# octanis_eps_v04.net
KiCad netlist of a schematic drawn in EAGLE
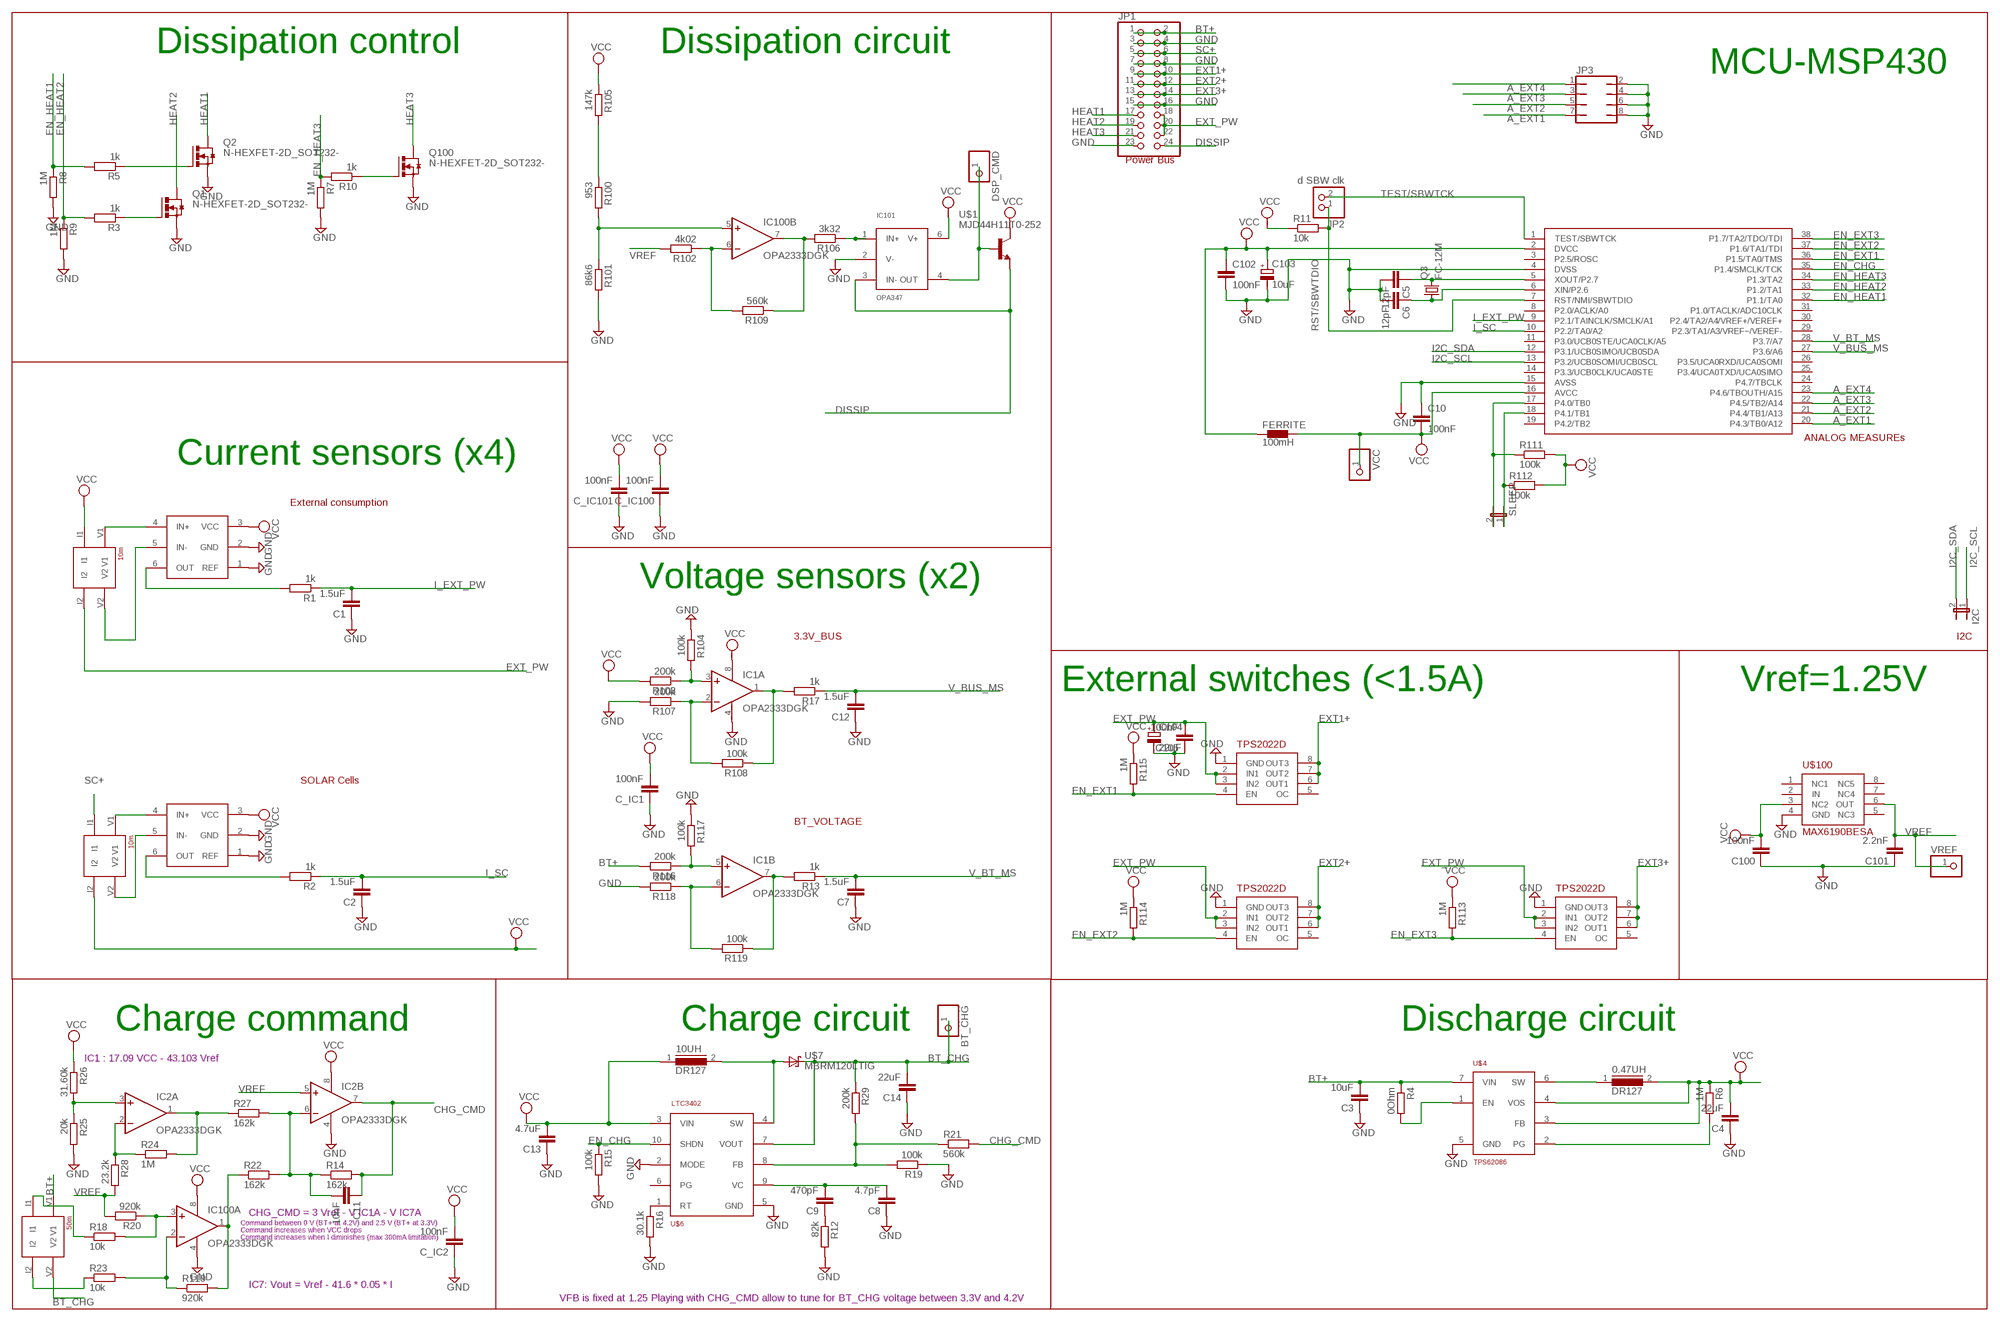
[diagram p0: schematic, sheet 1]

(export (version "E")
  (design (tool "Eeschema 10.0.6"))
  (components
    (comp (ref "0.47UH")
      (value "DR127")
      (footprint "eagle-import:DR127")
      (libsource (lib "eagle-import") (part "DR127"))
    )
    (comp (ref "10UH")
      (value "DR127")
      (footprint "eagle-import:DR127")
      (libsource (lib "eagle-import") (part "DR127"))
    )
    (comp (ref "BT_CHG")
      (value "PINHD-1X1")
      (footprint "eagle-import:1X01")
      (libsource (lib "eagle-import") (part "PINHD-1X1"))
    )
    (comp (ref "C1")
      (value "1.5uF")
      (footprint "eagle-import:C0603")
      (libsource (lib "eagle-import") (part "C-EUC0603"))
    )
    (comp (ref "C2")
      (value "1.5uF")
      (footprint "eagle-import:C0603")
      (libsource (lib "eagle-import") (part "C-EUC0603"))
    )
    (comp (ref "C3")
      (value "10uF")
      (footprint "eagle-import:C1206")
      (libsource (lib "eagle-import") (part "C-EUC1206"))
    )
    (comp (ref "C4")
      (value "22uF")
      (footprint "eagle-import:C1206")
      (libsource (lib "eagle-import") (part "C-EUC1206"))
    )
    (comp (ref "C5")
      (value "12pF")
      (footprint "eagle-import:C0603")
      (libsource (lib "eagle-import") (part "C-EUC0603"))
    )
    (comp (ref "C6")
      (value "12pF")
      (footprint "eagle-import:C0603")
      (libsource (lib "eagle-import") (part "C-EUC0603"))
    )
    (comp (ref "C7")
      (value "1.5uF")
      (footprint "eagle-import:C0603")
      (libsource (lib "eagle-import") (part "C-EUC0603"))
    )
    (comp (ref "C8")
      (value "4.7pF")
      (footprint "eagle-import:C0603")
      (libsource (lib "eagle-import") (part "C-EUC0603"))
    )
    (comp (ref "C9")
      (value "470pF")
      (footprint "eagle-import:C0603")
      (libsource (lib "eagle-import") (part "C-EUC0603"))
    )
    (comp (ref "C10")
      (value "100nF")
      (footprint "eagle-import:C0603")
      (libsource (lib "eagle-import") (part "C-EUC0603"))
    )
    (comp (ref "C11")
      (value "10nF")
      (footprint "eagle-import:C0603")
      (libsource (lib "eagle-import") (part "C-EUC0603"))
    )
    (comp (ref "C12")
      (value "1.5uF")
      (footprint "eagle-import:C0603")
      (libsource (lib "eagle-import") (part "C-EUC0603"))
    )
    (comp (ref "C13")
      (value "4.7uF")
      (footprint "eagle-import:C1206")
      (libsource (lib "eagle-import") (part "C-EUC1206"))
    )
    (comp (ref "C14")
      (value "22uF")
      (footprint "eagle-import:C0603")
      (libsource (lib "eagle-import") (part "C-EUC0603"))
    )
    (comp (ref "C100")
      (value "100nF")
      (footprint "eagle-import:C0603")
      (libsource (lib "eagle-import") (part "C-EUC0603"))
    )
    (comp (ref "C101")
      (value "2.2nF")
      (footprint "eagle-import:C0603")
      (libsource (lib "eagle-import") (part "C-EUC0603"))
    )
    (comp (ref "C102")
      (value "100nF")
      (footprint "eagle-import:C0603")
      (libsource (lib "eagle-import") (part "C-EUC0603"))
    )
    (comp (ref "C103")
      (value "10uF")
      (footprint "eagle-import:A_3216-18R")
      (libsource (lib "eagle-import") (part "CPOL-EUA/3216-18R"))
    )
    (comp (ref "C104")
      (value "22uF")
      (footprint "eagle-import:A_3216-18R")
      (libsource (lib "eagle-import") (part "CPOL-EUA/3216-18R"))
    )
    (comp (ref "C105")
      (value "100nF")
      (footprint "eagle-import:C0603")
      (libsource (lib "eagle-import") (part "C-EUC0603"))
    )
    (comp (ref "C_IC1")
      (value "100nF")
      (footprint "eagle-import:C0603")
      (libsource (lib "eagle-import") (part "C-EUC0603"))
    )
    (comp (ref "C_IC2")
      (value "100nF")
      (footprint "eagle-import:C0603")
      (libsource (lib "eagle-import") (part "C-EUC0603"))
    )
    (comp (ref "C_IC100")
      (value "100nF")
      (footprint "eagle-import:C0603")
      (libsource (lib "eagle-import") (part "C-EUC0603"))
    )
    (comp (ref "C_IC101")
      (value "100nF")
      (footprint "eagle-import:C0603")
      (libsource (lib "eagle-import") (part "C-EUC0603"))
    )
    (comp (ref "DSP_CMD")
      (value "PINHD-1X1")
      (footprint "eagle-import:1X01")
      (libsource (lib "eagle-import") (part "PINHD-1X1"))
    )
    (comp (ref "FERRITE")
      (value "100mH")
      (footprint "eagle-import:0402")
      (libsource (lib "eagle-import") (part "BLM15HD601SN1"))
    )
    (comp (ref "I2C")
      (value "JP1E")
      (footprint "eagle-import:JP1")
      (libsource (lib "eagle-import") (part "JP1E"))
    )
    (comp (ref "IC1")
      (value "OPA2333DGK")
      (footprint "eagle-import:MSOP08")
      (libsource (lib "eagle-import") (part "OPA2333DGK"))
    )
    (comp (ref "IC2")
      (value "OPA2333DGK")
      (footprint "eagle-import:MSOP08")
      (libsource (lib "eagle-import") (part "OPA2333DGK"))
    )
    (comp (ref "IC100")
      (value "OPA2333DGK")
      (footprint "eagle-import:MSOP08")
      (libsource (lib "eagle-import") (part "OPA2333DGK"))
    )
    (comp (ref "IC101")
      (value "OPA347")
      (footprint "eagle-import:SC70-5")
      (libsource (lib "eagle-import") (part "OPA347"))
    )
    (comp (ref "JP1")
      (value "PINHD-2X12")
      (footprint "eagle-import:2X12")
      (libsource (lib "eagle-import") (part "PINHD-2X12"))
    )
    (comp (ref "JP2")
      (value "d SBW clk")
      (footprint "eagle-import:1X02")
      (libsource (lib "eagle-import") (part "PINHD-1X2"))
    )
    (comp (ref "JP3")
      (value "JP4Q")
      (footprint "eagle-import:JP4Q")
      (libsource (lib "eagle-import") (part "JP4Q"))
    )
    (comp (ref "Q1")
      (value "N-HEXFET-2D_SOT232-")
      (footprint "eagle-import:SOT223")
      (libsource (lib "eagle-import") (part "N-HEXFET-2D_?-SOT232"))
    )
    (comp (ref "Q2")
      (value "N-HEXFET-2D_SOT232-")
      (footprint "eagle-import:SOT223")
      (libsource (lib "eagle-import") (part "N-HEXFET-2D_?-SOT232"))
    )
    (comp (ref "Q3")
      (value "FC-12M")
      (footprint "eagle-import:FC-12M")
      (libsource (lib "eagle-import") (part "FC-12M"))
    )
    (comp (ref "Q100")
      (value "N-HEXFET-2D_SOT232-")
      (footprint "eagle-import:SOT223")
      (libsource (lib "eagle-import") (part "N-HEXFET-2D_?-SOT232"))
    )
    (comp (ref "R1")
      (value "1k")
      (footprint "eagle-import:R0603")
      (libsource (lib "eagle-import") (part "R-EU_R0603"))
    )
    (comp (ref "R2")
      (value "1k")
      (footprint "eagle-import:R0603")
      (libsource (lib "eagle-import") (part "R-EU_R0603"))
    )
    (comp (ref "R3")
      (value "1k")
      (footprint "eagle-import:R0603")
      (libsource (lib "eagle-import") (part "R-EU_R0603"))
    )
    (comp (ref "R4")
      (value "0Ohm")
      (footprint "eagle-import:R0603")
      (libsource (lib "eagle-import") (part "R-EU_R0603"))
    )
    (comp (ref "R5")
      (value "1k")
      (footprint "eagle-import:R0603")
      (libsource (lib "eagle-import") (part "R-EU_R0603"))
    )
    (comp (ref "R6")
      (value "1M")
      (footprint "eagle-import:R0603")
      (libsource (lib "eagle-import") (part "R-EU_R0603"))
    )
    (comp (ref "R7")
      (value "1M")
      (footprint "eagle-import:R0603")
      (libsource (lib "eagle-import") (part "R-EU_R0603"))
    )
    (comp (ref "R8")
      (value "1M")
      (footprint "eagle-import:R0603")
      (libsource (lib "eagle-import") (part "R-EU_R0603"))
    )
    (comp (ref "R9")
      (value "1M")
      (footprint "eagle-import:R0603")
      (libsource (lib "eagle-import") (part "R-EU_R0603"))
    )
    (comp (ref "R10")
      (value "1k")
      (footprint "eagle-import:R0603")
      (libsource (lib "eagle-import") (part "R-EU_R0603"))
    )
    (comp (ref "R11")
      (value "10k")
      (footprint "eagle-import:R0603")
      (libsource (lib "eagle-import") (part "R-EU_R0603"))
    )
    (comp (ref "R12")
      (value "82k")
      (footprint "eagle-import:R0603")
      (libsource (lib "eagle-import") (part "R-EU_R0603"))
    )
    (comp (ref "R13")
      (value "1k")
      (footprint "eagle-import:R0603")
      (libsource (lib "eagle-import") (part "R-EU_R0603"))
    )
    (comp (ref "R14")
      (value "162k")
      (footprint "eagle-import:R0603")
      (libsource (lib "eagle-import") (part "R-EU_R0603"))
    )
    (comp (ref "R15")
      (value "100k")
      (footprint "eagle-import:R0603")
      (libsource (lib "eagle-import") (part "R-EU_R0603"))
    )
    (comp (ref "R16")
      (value "30.1k")
      (footprint "eagle-import:R0603")
      (libsource (lib "eagle-import") (part "R-EU_R0603"))
    )
    (comp (ref "R17")
      (value "1k")
      (footprint "eagle-import:R0603")
      (libsource (lib "eagle-import") (part "R-EU_R0603"))
    )
    (comp (ref "R18")
      (value "10k")
      (footprint "eagle-import:R0603")
      (libsource (lib "eagle-import") (part "R-EU_R0603"))
    )
    (comp (ref "R19")
      (value "100k")
      (footprint "eagle-import:R0603")
      (libsource (lib "eagle-import") (part "R-EU_R0603"))
    )
    (comp (ref "R20")
      (value "920k")
      (footprint "eagle-import:R0603")
      (libsource (lib "eagle-import") (part "R-EU_R0603"))
    )
    (comp (ref "R21")
      (value "560k")
      (footprint "eagle-import:R0603")
      (libsource (lib "eagle-import") (part "R-EU_R0603"))
    )
    (comp (ref "R22")
      (value "162k")
      (footprint "eagle-import:R0603")
      (libsource (lib "eagle-import") (part "R-EU_R0603"))
    )
    (comp (ref "R23")
      (value "10k")
      (footprint "eagle-import:R0603")
      (libsource (lib "eagle-import") (part "R-EU_R0603"))
    )
    (comp (ref "R24")
      (value "1M")
      (footprint "eagle-import:R0603")
      (libsource (lib "eagle-import") (part "R-EU_R0603"))
    )
    (comp (ref "R25")
      (value "20k")
      (footprint "eagle-import:R0603")
      (libsource (lib "eagle-import") (part "R-EU_R0603"))
    )
    (comp (ref "R26")
      (value "31.60k")
      (footprint "eagle-import:R0603")
      (libsource (lib "eagle-import") (part "R-EU_R0603"))
    )
    (comp (ref "R27")
      (value "162k")
      (footprint "eagle-import:R0603")
      (libsource (lib "eagle-import") (part "R-EU_R0603"))
    )
    (comp (ref "R28")
      (value "23.2k")
      (footprint "eagle-import:R0603")
      (libsource (lib "eagle-import") (part "R-EU_R0603"))
    )
    (comp (ref "R29")
      (value "200k")
      (footprint "eagle-import:R0603")
      (libsource (lib "eagle-import") (part "R-EU_R0603"))
    )
    (comp (ref "R100")
      (value "953")
      (footprint "eagle-import:R0603")
      (libsource (lib "eagle-import") (part "R-EU_R0603"))
    )
    (comp (ref "R101")
      (value "86k6")
      (footprint "eagle-import:R0603")
      (libsource (lib "eagle-import") (part "R-EU_R0603"))
    )
    (comp (ref "R102")
      (value "4k02")
      (footprint "eagle-import:R0603")
      (libsource (lib "eagle-import") (part "R-EU_R0603"))
    )
    (comp (ref "R103")
      (value "200k")
      (footprint "eagle-import:R0603")
      (libsource (lib "eagle-import") (part "R-EU_R0603"))
    )
    (comp (ref "R104")
      (value "100k")
      (footprint "eagle-import:R0603")
      (libsource (lib "eagle-import") (part "R-EU_R0603"))
    )
    (comp (ref "R105")
      (value "147k")
      (footprint "eagle-import:R0603")
      (libsource (lib "eagle-import") (part "R-EU_R0603"))
    )
    (comp (ref "R106")
      (value "3k32")
      (footprint "eagle-import:R0603")
      (libsource (lib "eagle-import") (part "R-EU_R0603"))
    )
    (comp (ref "R107")
      (value "200k")
      (footprint "eagle-import:R0603")
      (libsource (lib "eagle-import") (part "R-EU_R0603"))
    )
    (comp (ref "R108")
      (value "100k")
      (footprint "eagle-import:R0603")
      (libsource (lib "eagle-import") (part "R-EU_R0603"))
    )
    (comp (ref "R109")
      (value "560k")
      (footprint "eagle-import:R0603")
      (libsource (lib "eagle-import") (part "R-EU_R0603"))
    )
    (comp (ref "R110")
      (value "920k")
      (footprint "eagle-import:R0603")
      (libsource (lib "eagle-import") (part "R-EU_R0603"))
    )
    (comp (ref "R111")
      (value "100k")
      (footprint "eagle-import:R0603")
      (libsource (lib "eagle-import") (part "R-EU_R0603"))
    )
    (comp (ref "R112")
      (value "100k")
      (footprint "eagle-import:R0603")
      (libsource (lib "eagle-import") (part "R-EU_R0603"))
    )
    (comp (ref "R113")
      (value "1M")
      (footprint "eagle-import:R0603")
      (libsource (lib "eagle-import") (part "R-EU_R0603"))
    )
    (comp (ref "R114")
      (value "1M")
      (footprint "eagle-import:R0603")
      (libsource (lib "eagle-import") (part "R-EU_R0603"))
    )
    (comp (ref "R115")
      (value "1M")
      (footprint "eagle-import:R0603")
      (libsource (lib "eagle-import") (part "R-EU_R0603"))
    )
    (comp (ref "R116")
      (value "200k")
      (footprint "eagle-import:R0603")
      (libsource (lib "eagle-import") (part "R-EU_R0603"))
    )
    (comp (ref "R117")
      (value "100k")
      (footprint "eagle-import:R0603")
      (libsource (lib "eagle-import") (part "R-EU_R0603"))
    )
    (comp (ref "R118")
      (value "200k")
      (footprint "eagle-import:R0603")
      (libsource (lib "eagle-import") (part "R-EU_R0603"))
    )
    (comp (ref "R119")
      (value "100k")
      (footprint "eagle-import:R0603")
      (libsource (lib "eagle-import") (part "R-EU_R0603"))
    )
    (comp (ref "RSENSE1")
      (value "10m")
      (footprint "eagle-import:4PADS_RESISTOR")
      (libsource (lib "eagle-import") (part "CURRENT_RESISTOR"))
    )
    (comp (ref "RSENSE2")
      (value "50m")
      (footprint "eagle-import:4PADS_RESISTOR")
      (libsource (lib "eagle-import") (part "CURRENT_RESISTOR"))
    )
    (comp (ref "R_SENSE1")
      (value "10m")
      (footprint "eagle-import:4PADS_RESISTOR")
      (libsource (lib "eagle-import") (part "CURRENT_RESISTOR"))
    )
    (comp (ref "SLEEP")
      (value "JP1E")
      (footprint "eagle-import:JP1")
      (libsource (lib "eagle-import") (part "JP1E"))
    )
    (comp (ref "U$1")
      (value "MJD44H11T0-252")
      (footprint "eagle-import:TO252")
      (libsource (lib "eagle-import") (part "MJD44H11T0-252"))
    )
    (comp (ref "U$2")
      (value "INA213")
      (footprint "eagle-import:SC70-6")
      (libsource (lib "eagle-import") (part "INA213"))
    )
    (comp (ref "U$3")
      (value "INA213")
      (footprint "eagle-import:SC70-6")
      (libsource (lib "eagle-import") (part "INA213"))
    )
    (comp (ref "U$4")
      (value "TPS62086")
      (footprint "eagle-import:QFN-7")
      (libsource (lib "eagle-import") (part "TPS62086"))
    )
    (comp (ref "U$5")
      (value "MSP430G2544")
      (footprint "eagle-import:TSSOP38_MSPGXX44_SERIES")
      (libsource (lib "eagle-import") (part "MSP430G2544"))
    )
    (comp (ref "U$6")
      (value "LTC3402")
      (footprint "eagle-import:MSOP10")
      (libsource (lib "eagle-import") (part "LTC3402"))
    )
    (comp (ref "U$7")
      (value "MBRM120LTIG")
      (footprint "eagle-import:DO216AA")
      (libsource (lib "eagle-import") (part "MBRM120LTIG"))
    )
    (comp (ref "U$100")
      (value "MAX6190BESA")
      (footprint "eagle-import:SO8")
      (libsource (lib "eagle-import") (part "MAX6190BESA"))
    )
    (comp (ref "U$101")
      (value "TPS2022D")
      (footprint "eagle-import:SO8")
      (libsource (lib "eagle-import") (part "TPS2022D"))
    )
    (comp (ref "U$102")
      (value "TPS2022D")
      (footprint "eagle-import:SO8")
      (libsource (lib "eagle-import") (part "TPS2022D"))
    )
    (comp (ref "U$103")
      (value "TPS2022D")
      (footprint "eagle-import:SO8")
      (libsource (lib "eagle-import") (part "TPS2022D"))
    )
    (comp (ref "VCC")
      (value "PINHD-1X1")
      (footprint "eagle-import:1X01")
      (libsource (lib "eagle-import") (part "PINHD-1X1"))
    )
    (comp (ref "VREF")
      (value "PINHD-1X1")
      (footprint "eagle-import:1X01")
      (libsource (lib "eagle-import") (part "PINHD-1X1"))
    )
  )
  (nets
    (net (code "1") (name "/A_EXT1") (class "Default")
      (node (ref "JP3") (pin "7") (pinfunction "7_7") (pintype "passive"))
      (node (ref "U$5") (pin "20") (pinfunction "P4.3/TB0/A12_20") (pintype "bidirectional"))
    )
    (net (code "2") (name "/A_EXT2") (class "Default")
      (node (ref "JP3") (pin "5") (pinfunction "5_5") (pintype "passive"))
      (node (ref "U$5") (pin "21") (pinfunction "P4.4/TB1/A13_21") (pintype "bidirectional"))
    )
    (net (code "3") (name "/A_EXT3") (class "Default")
      (node (ref "JP3") (pin "3") (pinfunction "3_3") (pintype "passive"))
      (node (ref "U$5") (pin "22") (pinfunction "P4.5/TB2/A14_22") (pintype "bidirectional"))
    )
    (net (code "4") (name "/A_EXT4") (class "Default")
      (node (ref "JP3") (pin "1") (pinfunction "1_1") (pintype "passive"))
      (node (ref "U$5") (pin "23") (pinfunction "P4.6/TBOUTH/A15_23") (pintype "bidirectional"))
    )
    (net (code "5") (name "/BT+") (class "Default")
      (node (ref "C3") (pin "2") (pinfunction "2_2") (pintype "passive"))
      (node (ref "JP1") (pin "1") (pinfunction "1_1") (pintype "passive"))
      (node (ref "JP1") (pin "2") (pinfunction "2_2") (pintype "passive"))
      (node (ref "R116") (pin "2") (pinfunction "2_2") (pintype "passive"))
      (node (ref "R4") (pin "1") (pinfunction "1_1") (pintype "passive"))
      (node (ref "RSENSE2") (pin "V1") (pinfunction "V1_V1") (pintype "bidirectional"))
      (node (ref "U$4") (pin "7") (pinfunction "VIN_7") (pintype "bidirectional"))
    )
    (net (code "6") (name "/BT_CHG") (class "Default")
      (node (ref "BT_CHG") (pin "1") (pinfunction "1_1") (pintype "passive"))
      (node (ref "C14") (pin "2") (pinfunction "2_2") (pintype "passive"))
      (node (ref "R29") (pin "1") (pinfunction "1_1") (pintype "passive"))
      (node (ref "RSENSE2") (pin "V2") (pinfunction "V2_V2") (pintype "bidirectional"))
      (node (ref "U$6") (pin "7") (pinfunction "VOUT_7") (pintype "bidirectional"))
      (node (ref "U$7") (pin "C") (pinfunction "K_C") (pintype "passive"))
    )
    (net (code "7") (name "/CHG_CMD") (class "Default")
      (node (ref "C11") (pin "1") (pinfunction "1_1") (pintype "passive"))
      (node (ref "IC2") (pin "7") (pinfunction "OUT_7") (pintype "output"))
      (node (ref "R14") (pin "2") (pinfunction "2_2") (pintype "passive"))
      (node (ref "R21") (pin "2") (pinfunction "2_2") (pintype "passive"))
    )
    (net (code "8") (name "/DISSIP") (class "Default")
      (node (ref "IC101") (pin "3") (pinfunction "IN-_3") (pintype "bidirectional"))
      (node (ref "JP1") (pin "24") (pinfunction "24_24") (pintype "passive"))
      (node (ref "U$1") (pin "3") (pinfunction "E_3") (pintype "passive"))
    )
    (net (code "9") (name "/EN_CHG") (class "Default")
      (node (ref "R15") (pin "1") (pinfunction "1_1") (pintype "passive"))
      (node (ref "U$5") (pin "35") (pinfunction "P1.4/SMCLK/TCK_35") (pintype "bidirectional"))
      (node (ref "U$6") (pin "10") (pinfunction "SHDN_10") (pintype "bidirectional"))
    )
    (net (code "10") (name "/EN_EXT1") (class "Default")
      (node (ref "R115") (pin "2") (pinfunction "2_2") (pintype "passive"))
      (node (ref "U$103") (pin "4") (pinfunction "EN_4") (pintype "bidirectional"))
      (node (ref "U$5") (pin "36") (pinfunction "P1.5/TA0/TMS_36") (pintype "bidirectional"))
    )
    (net (code "11") (name "/EN_EXT2") (class "Default")
      (node (ref "R114") (pin "2") (pinfunction "2_2") (pintype "passive"))
      (node (ref "U$102") (pin "4") (pinfunction "EN_4") (pintype "bidirectional"))
      (node (ref "U$5") (pin "37") (pinfunction "P1.6/TA1/TDI_37") (pintype "bidirectional"))
    )
    (net (code "12") (name "/EN_EXT3") (class "Default")
      (node (ref "R113") (pin "2") (pinfunction "2_2") (pintype "passive"))
      (node (ref "U$101") (pin "4") (pinfunction "EN_4") (pintype "bidirectional"))
      (node (ref "U$5") (pin "38") (pinfunction "P1.7/TA2/TDO/TDI_38") (pintype "bidirectional"))
    )
    (net (code "13") (name "/EN_HEAT1") (class "Default")
      (node (ref "R5") (pin "2") (pinfunction "2_2") (pintype "passive"))
      (node (ref "R8") (pin "1") (pinfunction "1_1") (pintype "passive"))
      (node (ref "U$5") (pin "32") (pinfunction "P1.1/TA0_32") (pintype "bidirectional"))
    )
    (net (code "14") (name "/EN_HEAT2") (class "Default")
      (node (ref "R3") (pin "2") (pinfunction "2_2") (pintype "passive"))
      (node (ref "R9") (pin "1") (pinfunction "1_1") (pintype "passive"))
      (node (ref "U$5") (pin "33") (pinfunction "P1.2/TA1_33") (pintype "bidirectional"))
    )
    (net (code "15") (name "/EN_HEAT3") (class "Default")
      (node (ref "R10") (pin "2") (pinfunction "2_2") (pintype "passive"))
      (node (ref "R7") (pin "1") (pinfunction "1_1") (pintype "passive"))
      (node (ref "U$5") (pin "34") (pinfunction "P1.3/TA2_34") (pintype "bidirectional"))
    )
    (net (code "16") (name "/EXT1+") (class "Default")
      (node (ref "JP1") (pin "10") (pinfunction "10_10") (pintype "passive"))
      (node (ref "JP1") (pin "9") (pinfunction "9_9") (pintype "passive"))
      (node (ref "U$103") (pin "6") (pinfunction "OUT1_6") (pintype "bidirectional"))
      (node (ref "U$103") (pin "7") (pinfunction "OUT2_7") (pintype "bidirectional"))
      (node (ref "U$103") (pin "8") (pinfunction "OUT3_8") (pintype "bidirectional"))
    )
    (net (code "17") (name "/EXT2+") (class "Default")
      (node (ref "JP1") (pin "11") (pinfunction "11_11") (pintype "passive"))
      (node (ref "JP1") (pin "12") (pinfunction "12_12") (pintype "passive"))
      (node (ref "U$102") (pin "6") (pinfunction "OUT1_6") (pintype "bidirectional"))
      (node (ref "U$102") (pin "7") (pinfunction "OUT2_7") (pintype "bidirectional"))
      (node (ref "U$102") (pin "8") (pinfunction "OUT3_8") (pintype "bidirectional"))
    )
    (net (code "18") (name "/EXT3+") (class "Default")
      (node (ref "JP1") (pin "13") (pinfunction "13_13") (pintype "passive"))
      (node (ref "JP1") (pin "14") (pinfunction "14_14") (pintype "passive"))
      (node (ref "U$101") (pin "6") (pinfunction "OUT1_6") (pintype "bidirectional"))
      (node (ref "U$101") (pin "7") (pinfunction "OUT2_7") (pintype "bidirectional"))
      (node (ref "U$101") (pin "8") (pinfunction "OUT3_8") (pintype "bidirectional"))
    )
    (net (code "19") (name "/EXT_PW") (class "Default")
      (node (ref "C104") (pin "+") (pinfunction "+_+") (pintype "passive"))
      (node (ref "C105") (pin "2") (pinfunction "2_2") (pintype "passive"))
      (node (ref "JP1") (pin "18") (pinfunction "18_18") (pintype "passive"))
      (node (ref "JP1") (pin "20") (pinfunction "20_20") (pintype "passive"))
      (node (ref "JP1") (pin "22") (pinfunction "22_22") (pintype "passive"))
      (node (ref "R_SENSE1") (pin "I2") (pinfunction "I2_I2") (pintype "bidirectional"))
      (node (ref "U$101") (pin "2") (pinfunction "IN1_2") (pintype "bidirectional"))
      (node (ref "U$101") (pin "3") (pinfunction "IN2_3") (pintype "bidirectional"))
      (node (ref "U$102") (pin "2") (pinfunction "IN1_2") (pintype "bidirectional"))
      (node (ref "U$102") (pin "3") (pinfunction "IN2_3") (pintype "bidirectional"))
      (node (ref "U$103") (pin "2") (pinfunction "IN1_2") (pintype "bidirectional"))
      (node (ref "U$103") (pin "3") (pinfunction "IN2_3") (pintype "bidirectional"))
    )
    (net (code "20") (name "/HEAT1") (class "Default")
      (node (ref "JP1") (pin "17") (pinfunction "17_17") (pintype "passive"))
      (node (ref "Q2") (pin "2") (pinfunction "D_2") (pintype "passive"))
      (node (ref "Q2") (pin "4") (pinfunction "D_4") (pintype "passive"))
    )
    (net (code "21") (name "/HEAT2") (class "Default")
      (node (ref "JP1") (pin "19") (pinfunction "19_19") (pintype "passive"))
      (node (ref "Q1") (pin "2") (pinfunction "D_2") (pintype "passive"))
      (node (ref "Q1") (pin "4") (pinfunction "D_4") (pintype "passive"))
    )
    (net (code "22") (name "/HEAT3") (class "Default")
      (node (ref "JP1") (pin "21") (pinfunction "21_21") (pintype "passive"))
      (node (ref "Q100") (pin "2") (pinfunction "D_2") (pintype "passive"))
      (node (ref "Q100") (pin "4") (pinfunction "D_4") (pintype "passive"))
    )
    (net (code "23") (name "/I2C_SCL") (class "Default")
      (node (ref "I2C") (pin "1") (pinfunction "1_1") (pintype "passive"))
      (node (ref "U$5") (pin "13") (pinfunction "P3.2/UCB0SOMI/UCB0SCL_13") (pintype "bidirectional"))
    )
    (net (code "24") (name "/I2C_SDA") (class "Default")
      (node (ref "I2C") (pin "2") (pinfunction "2_2") (pintype "passive"))
      (node (ref "U$5") (pin "12") (pinfunction "P3.1/UCB0SIMO/UCB0SDA_12") (pintype "bidirectional"))
    )
    (net (code "25") (name "/I_EXT_PW") (class "Default")
      (node (ref "C1") (pin "2") (pinfunction "2_2") (pintype "passive"))
      (node (ref "R1") (pin "1") (pinfunction "1_1") (pintype "passive"))
      (node (ref "U$5") (pin "9") (pinfunction "P2.1/TAINCLK/SMCLK/A1_9") (pintype "bidirectional"))
    )
    (net (code "26") (name "/I_SC") (class "Default")
      (node (ref "C2") (pin "2") (pinfunction "2_2") (pintype "passive"))
      (node (ref "R2") (pin "1") (pinfunction "1_1") (pintype "passive"))
      (node (ref "U$5") (pin "10") (pinfunction "P2.2/TA0/A2_10") (pintype "bidirectional"))
    )
    (net (code "27") (name "/RST{slash}SBWTDIO") (class "Default")
      (node (ref "JP2") (pin "1") (pinfunction "1_1") (pintype "passive"))
      (node (ref "R11") (pin "2") (pinfunction "2_2") (pintype "passive"))
      (node (ref "U$5") (pin "7") (pinfunction "RST/NMI/SBWTDIO_7") (pintype "bidirectional"))
    )
    (net (code "28") (name "/SC+") (class "Default")
      (node (ref "JP1") (pin "5") (pinfunction "5_5") (pintype "passive"))
      (node (ref "JP1") (pin "6") (pinfunction "6_6") (pintype "passive"))
      (node (ref "RSENSE1") (pin "I1") (pinfunction "I1_I1") (pintype "bidirectional"))
    )
    (net (code "29") (name "/TEST{slash}SBWTCK") (class "Default")
      (node (ref "JP2") (pin "2") (pinfunction "2_2") (pintype "passive"))
      (node (ref "U$5") (pin "1") (pinfunction "TEST/SBWTCK_1") (pintype "bidirectional"))
    )
    (net (code "30") (name "/VREF") (class "Default")
      (node (ref "C101") (pin "2") (pinfunction "2_2") (pintype "passive"))
      (node (ref "IC2") (pin "5") (pinfunction "+IN_5") (pintype "input"))
      (node (ref "R102") (pin "2") (pinfunction "2_2") (pintype "passive"))
      (node (ref "R20") (pin "2") (pinfunction "2_2") (pintype "passive"))
      (node (ref "R28") (pin "2") (pinfunction "2_2") (pintype "passive"))
      (node (ref "U$100") (pin "6") (pinfunction "OUT_6") (pintype "bidirectional"))
      (node (ref "VREF") (pin "1") (pinfunction "1_1") (pintype "passive"))
    )
    (net (code "31") (name "/V_BT_MS") (class "Default")
      (node (ref "C7") (pin "2") (pinfunction "2_2") (pintype "passive"))
      (node (ref "R13") (pin "1") (pinfunction "1_1") (pintype "passive"))
      (node (ref "U$5") (pin "28") (pinfunction "P3.7/A7_28") (pintype "bidirectional"))
    )
    (net (code "32") (name "/V_BUS_MS") (class "Default")
      (node (ref "C12") (pin "2") (pinfunction "2_2") (pintype "passive"))
      (node (ref "R17") (pin "1") (pinfunction "1_1") (pintype "passive"))
      (node (ref "U$5") (pin "27") (pinfunction "P3.6/A6_27") (pintype "bidirectional"))
    )
    (net (code "33") (name "GND") (class "Default")
      (node (ref "C1") (pin "1") (pinfunction "1_1") (pintype "passive"))
      (node (ref "C10") (pin "1") (pinfunction "1_1") (pintype "passive"))
      (node (ref "C100") (pin "1") (pinfunction "1_1") (pintype "passive"))
      (node (ref "C101") (pin "1") (pinfunction "1_1") (pintype "passive"))
      (node (ref "C102") (pin "2") (pinfunction "2_2") (pintype "passive"))
      (node (ref "C103") (pin "-") (pinfunction "-_-") (pintype "passive"))
      (node (ref "C104") (pin "-") (pinfunction "-_-") (pintype "passive"))
      (node (ref "C105") (pin "1") (pinfunction "1_1") (pintype "passive"))
      (node (ref "C12") (pin "1") (pinfunction "1_1") (pintype "passive"))
      (node (ref "C13") (pin "1") (pinfunction "1_1") (pintype "passive"))
      (node (ref "C14") (pin "1") (pinfunction "1_1") (pintype "passive"))
      (node (ref "C2") (pin "1") (pinfunction "1_1") (pintype "passive"))
      (node (ref "C3") (pin "1") (pinfunction "1_1") (pintype "passive"))
      (node (ref "C4") (pin "1") (pinfunction "1_1") (pintype "passive"))
      (node (ref "C5") (pin "2") (pinfunction "2_2") (pintype "passive"))
      (node (ref "C6") (pin "2") (pinfunction "2_2") (pintype "passive"))
      (node (ref "C7") (pin "1") (pinfunction "1_1") (pintype "passive"))
      (node (ref "C8") (pin "1") (pinfunction "1_1") (pintype "passive"))
      (node (ref "C_IC1") (pin "1") (pinfunction "1_1") (pintype "passive"))
      (node (ref "C_IC100") (pin "1") (pinfunction "1_1") (pintype "passive"))
      (node (ref "C_IC101") (pin "1") (pinfunction "1_1") (pintype "passive"))
      (node (ref "C_IC2") (pin "1") (pinfunction "1_1") (pintype "passive"))
      (node (ref "IC1") (pin "4") (pinfunction "V-_4") (pintype "power_in"))
      (node (ref "IC100") (pin "4") (pinfunction "V-_4") (pintype "power_in"))
      (node (ref "IC101") (pin "2") (pinfunction "V-_2") (pintype "bidirectional"))
      (node (ref "IC2") (pin "4") (pinfunction "V-_4") (pintype "power_in"))
      (node (ref "JP1") (pin "15") (pinfunction "15_15") (pintype "passive"))
      (node (ref "JP1") (pin "16") (pinfunction "16_16") (pintype "passive"))
      (node (ref "JP1") (pin "23") (pinfunction "23_23") (pintype "passive"))
      (node (ref "JP1") (pin "3") (pinfunction "3_3") (pintype "passive"))
      (node (ref "JP1") (pin "4") (pinfunction "4_4") (pintype "passive"))
      (node (ref "JP1") (pin "7") (pinfunction "7_7") (pintype "passive"))
      (node (ref "JP1") (pin "8") (pinfunction "8_8") (pintype "passive"))
      (node (ref "JP3") (pin "2") (pinfunction "2_2") (pintype "passive"))
      (node (ref "JP3") (pin "4") (pinfunction "4_4") (pintype "passive"))
      (node (ref "JP3") (pin "6") (pinfunction "6_6") (pintype "passive"))
      (node (ref "JP3") (pin "8") (pinfunction "8_8") (pintype "passive"))
      (node (ref "Q1") (pin "3") (pinfunction "S_3") (pintype "passive"))
      (node (ref "Q100") (pin "3") (pinfunction "S_3") (pintype "passive"))
      (node (ref "Q2") (pin "3") (pinfunction "S_3") (pintype "passive"))
      (node (ref "R101") (pin "2") (pinfunction "2_2") (pintype "passive"))
      (node (ref "R104") (pin "1") (pinfunction "1_1") (pintype "passive"))
      (node (ref "R107") (pin "2") (pinfunction "2_2") (pintype "passive"))
      (node (ref "R117") (pin "1") (pinfunction "1_1") (pintype "passive"))
      (node (ref "R118") (pin "2") (pinfunction "2_2") (pintype "passive"))
      (node (ref "R12") (pin "2") (pinfunction "2_2") (pintype "passive"))
      (node (ref "R15") (pin "2") (pinfunction "2_2") (pintype "passive"))
      (node (ref "R16") (pin "2") (pinfunction "2_2") (pintype "passive"))
      (node (ref "R19") (pin "1") (pinfunction "1_1") (pintype "passive"))
      (node (ref "R25") (pin "2") (pinfunction "2_2") (pintype "passive"))
      (node (ref "R7") (pin "2") (pinfunction "2_2") (pintype "passive"))
      (node (ref "R8") (pin "2") (pinfunction "2_2") (pintype "passive"))
      (node (ref "R9") (pin "2") (pinfunction "2_2") (pintype "passive"))
      (node (ref "U$100") (pin "4") (pinfunction "GND_4") (pintype "bidirectional"))
      (node (ref "U$101") (pin "1") (pinfunction "GND_1") (pintype "bidirectional"))
      (node (ref "U$102") (pin "1") (pinfunction "GND_1") (pintype "bidirectional"))
      (node (ref "U$103") (pin "1") (pinfunction "GND_1") (pintype "bidirectional"))
      (node (ref "U$2") (pin "1") (pinfunction "REF_1") (pintype "bidirectional"))
      (node (ref "U$2") (pin "2") (pinfunction "GND_2") (pintype "bidirectional"))
      (node (ref "U$3") (pin "1") (pinfunction "REF_1") (pintype "bidirectional"))
      (node (ref "U$3") (pin "2") (pinfunction "GND_2") (pintype "bidirectional"))
      (node (ref "U$4") (pin "5") (pinfunction "GND_5") (pintype "bidirectional"))
      (node (ref "U$5") (pin "15") (pinfunction "AVSS_15") (pintype "bidirectional"))
      (node (ref "U$5") (pin "4") (pinfunction "DVSS_4") (pintype "bidirectional"))
      (node (ref "U$6") (pin "2") (pinfunction "MODE_2") (pintype "bidirectional"))
      (node (ref "U$6") (pin "5") (pinfunction "GND_5") (pintype "bidirectional"))
    )
    (net (code "34") (name "Net-(C9-Pad1)") (class "Default")
      (node (ref "C9") (pin "1") (pinfunction "1_1") (pintype "passive"))
      (node (ref "R12") (pin "1") (pinfunction "1_1") (pintype "passive"))
    )
    (net (code "35") (name "Net-(IC1A-+IN)") (class "Default")
      (node (ref "IC1") (pin "3") (pinfunction "+IN_3") (pintype "input"))
      (node (ref "R103") (pin "1") (pinfunction "1_1") (pintype "passive"))
      (node (ref "R104") (pin "2") (pinfunction "2_2") (pintype "passive"))
    )
    (net (code "36") (name "Net-(IC1A--IN)") (class "Default")
      (node (ref "IC1") (pin "2") (pinfunction "-IN_2") (pintype "input"))
      (node (ref "R107") (pin "1") (pinfunction "1_1") (pintype "passive"))
      (node (ref "R108") (pin "2") (pinfunction "2_2") (pintype "passive"))
    )
    (net (code "37") (name "Net-(IC1A-OUT)") (class "Default")
      (node (ref "IC1") (pin "1") (pinfunction "OUT_1") (pintype "output"))
      (node (ref "R108") (pin "1") (pinfunction "1_1") (pintype "passive"))
      (node (ref "R17") (pin "2") (pinfunction "2_2") (pintype "passive"))
    )
    (net (code "38") (name "Net-(IC1B-+IN)") (class "Default")
      (node (ref "IC1") (pin "5") (pinfunction "+IN_5") (pintype "input"))
      (node (ref "R116") (pin "1") (pinfunction "1_1") (pintype "passive"))
      (node (ref "R117") (pin "2") (pinfunction "2_2") (pintype "passive"))
    )
    (net (code "39") (name "Net-(IC1B--IN)") (class "Default")
      (node (ref "IC1") (pin "6") (pinfunction "-IN_6") (pintype "input"))
      (node (ref "R118") (pin "1") (pinfunction "1_1") (pintype "passive"))
      (node (ref "R119") (pin "2") (pinfunction "2_2") (pintype "passive"))
    )
    (net (code "40") (name "Net-(IC1B-OUT)") (class "Default")
      (node (ref "IC1") (pin "7") (pinfunction "OUT_7") (pintype "output"))
      (node (ref "R119") (pin "1") (pinfunction "1_1") (pintype "passive"))
      (node (ref "R13") (pin "2") (pinfunction "2_2") (pintype "passive"))
    )
    (net (code "41") (name "Net-(IC2A-+IN)") (class "Default")
      (node (ref "IC2") (pin "3") (pinfunction "+IN_3") (pintype "input"))
      (node (ref "R25") (pin "1") (pinfunction "1_1") (pintype "passive"))
      (node (ref "R26") (pin "2") (pinfunction "2_2") (pintype "passive"))
    )
    (net (code "42") (name "Net-(IC2A--IN)") (class "Default")
      (node (ref "IC2") (pin "2") (pinfunction "-IN_2") (pintype "input"))
      (node (ref "R24") (pin "1") (pinfunction "1_1") (pintype "passive"))
      (node (ref "R28") (pin "1") (pinfunction "1_1") (pintype "passive"))
    )
    (net (code "43") (name "Net-(IC2A-OUT)") (class "Default")
      (node (ref "IC2") (pin "1") (pinfunction "OUT_1") (pintype "output"))
      (node (ref "R24") (pin "2") (pinfunction "2_2") (pintype "passive"))
      (node (ref "R27") (pin "1") (pinfunction "1_1") (pintype "passive"))
    )
    (net (code "44") (name "Net-(IC2B--IN)") (class "Default")
      (node (ref "C11") (pin "2") (pinfunction "2_2") (pintype "passive"))
      (node (ref "IC2") (pin "6") (pinfunction "-IN_6") (pintype "input"))
      (node (ref "R14") (pin "1") (pinfunction "1_1") (pintype "passive"))
      (node (ref "R22") (pin "2") (pinfunction "2_2") (pintype "passive"))
      (node (ref "R27") (pin "2") (pinfunction "2_2") (pintype "passive"))
    )
    (net (code "45") (name "Net-(IC100A-+IN)") (class "Default")
      (node (ref "IC100") (pin "3") (pinfunction "+IN_3") (pintype "input"))
      (node (ref "R18") (pin "2") (pinfunction "2_2") (pintype "passive"))
      (node (ref "R20") (pin "1") (pinfunction "1_1") (pintype "passive"))
    )
    (net (code "46") (name "Net-(IC100A--IN)") (class "Default")
      (node (ref "IC100") (pin "2") (pinfunction "-IN_2") (pintype "input"))
      (node (ref "R110") (pin "1") (pinfunction "1_1") (pintype "passive"))
      (node (ref "R23") (pin "2") (pinfunction "2_2") (pintype "passive"))
    )
    (net (code "47") (name "Net-(IC100A-OUT)") (class "Default")
      (node (ref "IC100") (pin "1") (pinfunction "OUT_1") (pintype "output"))
      (node (ref "R110") (pin "2") (pinfunction "2_2") (pintype "passive"))
      (node (ref "R22") (pin "1") (pinfunction "1_1") (pintype "passive"))
    )
    (net (code "48") (name "Net-(IC100B-+IN)") (class "Default")
      (node (ref "IC100") (pin "5") (pinfunction "+IN_5") (pintype "input"))
      (node (ref "R100") (pin "2") (pinfunction "2_2") (pintype "passive"))
      (node (ref "R101") (pin "1") (pinfunction "1_1") (pintype "passive"))
    )
    (net (code "49") (name "Net-(IC100B--IN)") (class "Default")
      (node (ref "IC100") (pin "6") (pinfunction "-IN_6") (pintype "input"))
      (node (ref "R102") (pin "1") (pinfunction "1_1") (pintype "passive"))
      (node (ref "R109") (pin "2") (pinfunction "2_2") (pintype "passive"))
    )
    (net (code "50") (name "Net-(IC100B-OUT)") (class "Default")
      (node (ref "IC100") (pin "7") (pinfunction "OUT_7") (pintype "output"))
      (node (ref "R106") (pin "2") (pinfunction "2_2") (pintype "passive"))
      (node (ref "R109") (pin "1") (pinfunction "1_1") (pintype "passive"))
    )
    (net (code "51") (name "Net-(IC101-IN+)") (class "Default")
      (node (ref "IC101") (pin "1") (pinfunction "IN+_1") (pintype "bidirectional"))
      (node (ref "R106") (pin "1") (pinfunction "1_1") (pintype "passive"))
    )
    (net (code "52") (name "Net-(IC101-OUT)") (class "Default")
      (node (ref "DSP_CMD") (pin "1") (pinfunction "1_1") (pintype "passive"))
      (node (ref "IC101") (pin "4") (pinfunction "OUT_4") (pintype "bidirectional"))
      (node (ref "U$1") (pin "1") (pinfunction "B_1") (pintype "passive"))
    )
    (net (code "53") (name "Net-(Q1-G)") (class "Default")
      (node (ref "Q1") (pin "1") (pinfunction "G_1") (pintype "passive"))
      (node (ref "R3") (pin "1") (pinfunction "1_1") (pintype "passive"))
    )
    (net (code "54") (name "Net-(Q2-G)") (class "Default")
      (node (ref "Q2") (pin "1") (pinfunction "G_1") (pintype "passive"))
      (node (ref "R5") (pin "1") (pinfunction "1_1") (pintype "passive"))
    )
    (net (code "55") (name "Net-(Q100-G)") (class "Default")
      (node (ref "Q100") (pin "1") (pinfunction "G_1") (pintype "passive"))
      (node (ref "R10") (pin "1") (pinfunction "1_1") (pintype "passive"))
    )
    (net (code "56") (name "Net-(R18-Pad1)") (class "Default")
      (node (ref "R18") (pin "1") (pinfunction "1_1") (pintype "passive"))
      (node (ref "RSENSE2") (pin "I1") (pinfunction "I1_I1") (pintype "bidirectional"))
    )
    (net (code "57") (name "Net-(R23-Pad1)") (class "Default")
      (node (ref "R23") (pin "1") (pinfunction "1_1") (pintype "passive"))
      (node (ref "RSENSE2") (pin "I2") (pinfunction "I2_I2") (pintype "bidirectional"))
    )
    (net (code "58") (name "Net-(R100-Pad1)") (class "Default")
      (node (ref "R100") (pin "1") (pinfunction "1_1") (pintype "passive"))
      (node (ref "R105") (pin "2") (pinfunction "2_2") (pintype "passive"))
    )
    (net (code "59") (name "Net-(U$2-IN+)") (class "Default")
      (node (ref "RSENSE1") (pin "V1") (pinfunction "V1_V1") (pintype "bidirectional"))
      (node (ref "U$2") (pin "4") (pinfunction "IN+_4") (pintype "bidirectional"))
    )
    (net (code "60") (name "Net-(U$2-IN-)") (class "Default")
      (node (ref "RSENSE1") (pin "V2") (pinfunction "V2_V2") (pintype "bidirectional"))
      (node (ref "U$2") (pin "5") (pinfunction "IN-_5") (pintype "bidirectional"))
    )
    (net (code "61") (name "Net-(U$2-OUT)") (class "Default")
      (node (ref "R2") (pin "2") (pinfunction "2_2") (pintype "passive"))
      (node (ref "U$2") (pin "6") (pinfunction "OUT_6") (pintype "bidirectional"))
    )
    (net (code "62") (name "Net-(U$3-IN+)") (class "Default")
      (node (ref "R_SENSE1") (pin "V1") (pinfunction "V1_V1") (pintype "bidirectional"))
      (node (ref "U$3") (pin "4") (pinfunction "IN+_4") (pintype "bidirectional"))
    )
    (net (code "63") (name "Net-(U$3-IN-)") (class "Default")
      (node (ref "R_SENSE1") (pin "V2") (pinfunction "V2_V2") (pintype "bidirectional"))
      (node (ref "U$3") (pin "5") (pinfunction "IN-_5") (pintype "bidirectional"))
    )
    (net (code "64") (name "Net-(U$3-OUT)") (class "Default")
      (node (ref "R1") (pin "2") (pinfunction "2_2") (pintype "passive"))
      (node (ref "U$3") (pin "6") (pinfunction "OUT_6") (pintype "bidirectional"))
    )
    (net (code "65") (name "Net-(U$4-EN)") (class "Default")
      (node (ref "R4") (pin "2") (pinfunction "2_2") (pintype "passive"))
      (node (ref "U$4") (pin "1") (pinfunction "EN_1") (pintype "bidirectional"))
    )
    (net (code "66") (name "Net-(U$4-PG)") (class "Default")
      (node (ref "R6") (pin "2") (pinfunction "2_2") (pintype "passive"))
      (node (ref "U$4") (pin "2") (pinfunction "PG_2") (pintype "bidirectional"))
    )
    (net (code "67") (name "Net-(U$4-SW)") (class "Default")
      (node (ref "0.47UH") (pin "1") (pinfunction "1_1") (pintype "passive"))
      (node (ref "U$4") (pin "6") (pinfunction "SW_6") (pintype "bidirectional"))
    )
    (net (code "68") (name "Net-(U$5-P4.0{slash}TB0)") (class "Default")
      (node (ref "R111") (pin "1") (pinfunction "1_1") (pintype "passive"))
      (node (ref "SLEEP") (pin "2") (pinfunction "2_2") (pintype "passive"))
      (node (ref "U$5") (pin "17") (pinfunction "P4.0/TB0_17") (pintype "bidirectional"))
    )
    (net (code "69") (name "Net-(U$5-P4.1{slash}TB1)") (class "Default")
      (node (ref "R112") (pin "1") (pinfunction "1_1") (pintype "passive"))
      (node (ref "SLEEP") (pin "1") (pinfunction "1_1") (pintype "passive"))
      (node (ref "U$5") (pin "18") (pinfunction "P4.1/TB1_18") (pintype "bidirectional"))
    )
    (net (code "70") (name "Net-(U$5-XIN{slash}P2.6)") (class "Default")
      (node (ref "C6") (pin "1") (pinfunction "1_1") (pintype "passive"))
      (node (ref "Q3") (pin "1") (pinfunction "1_1") (pintype "passive"))
      (node (ref "U$5") (pin "6") (pinfunction "XIN/P2.6_6") (pintype "bidirectional"))
    )
    (net (code "71") (name "Net-(U$5-XOUT{slash}P2.7)") (class "Default")
      (node (ref "C5") (pin "1") (pinfunction "1_1") (pintype "passive"))
      (node (ref "Q3") (pin "2") (pinfunction "2_2") (pintype "passive"))
      (node (ref "U$5") (pin "5") (pinfunction "XOUT/P2.7_5") (pintype "bidirectional"))
    )
    (net (code "72") (name "Net-(U$6-FB)") (class "Default")
      (node (ref "R19") (pin "2") (pinfunction "2_2") (pintype "passive"))
      (node (ref "R21") (pin "1") (pinfunction "1_1") (pintype "passive"))
      (node (ref "R29") (pin "2") (pinfunction "2_2") (pintype "passive"))
      (node (ref "U$6") (pin "8") (pinfunction "FB_8") (pintype "bidirectional"))
    )
    (net (code "73") (name "Net-(U$6-RT)") (class "Default")
      (node (ref "R16") (pin "1") (pinfunction "1_1") (pintype "passive"))
      (node (ref "U$6") (pin "1") (pinfunction "RT_1") (pintype "bidirectional"))
    )
    (net (code "74") (name "Net-(U$6-SW)") (class "Default")
      (node (ref "10UH") (pin "2") (pinfunction "2_2") (pintype "passive"))
      (node (ref "U$6") (pin "4") (pinfunction "SW_4") (pintype "bidirectional"))
      (node (ref "U$7") (pin "A") (pinfunction "A_A") (pintype "passive"))
    )
    (net (code "75") (name "Net-(U$6-VC)") (class "Default")
      (node (ref "C8") (pin "2") (pinfunction "2_2") (pintype "passive"))
      (node (ref "C9") (pin "2") (pinfunction "2_2") (pintype "passive"))
      (node (ref "U$6") (pin "9") (pinfunction "VC_9") (pintype "bidirectional"))
    )
    (net (code "76") (name "VCC") (class "Default")
      (node (ref "0.47UH") (pin "2") (pinfunction "2_2") (pintype "passive"))
      (node (ref "10UH") (pin "1") (pinfunction "1_1") (pintype "passive"))
      (node (ref "C10") (pin "2") (pinfunction "2_2") (pintype "passive"))
      (node (ref "C100") (pin "2") (pinfunction "2_2") (pintype "passive"))
      (node (ref "C102") (pin "1") (pinfunction "1_1") (pintype "passive"))
      (node (ref "C103") (pin "+") (pinfunction "+_+") (pintype "passive"))
      (node (ref "C13") (pin "2") (pinfunction "2_2") (pintype "passive"))
      (node (ref "C4") (pin "2") (pinfunction "2_2") (pintype "passive"))
      (node (ref "C_IC1") (pin "2") (pinfunction "2_2") (pintype "passive"))
      (node (ref "C_IC100") (pin "2") (pinfunction "2_2") (pintype "passive"))
      (node (ref "C_IC101") (pin "2") (pinfunction "2_2") (pintype "passive"))
      (node (ref "C_IC2") (pin "2") (pinfunction "2_2") (pintype "passive"))
      (node (ref "FERRITE") (pin "1") (pinfunction "1_1") (pintype "passive"))
      (node (ref "FERRITE") (pin "2") (pinfunction "2_2") (pintype "passive"))
      (node (ref "IC1") (pin "8") (pinfunction "V+_8") (pintype "power_in"))
      (node (ref "IC100") (pin "8") (pinfunction "V+_8") (pintype "power_in"))
      (node (ref "IC101") (pin "6") (pinfunction "V+_6") (pintype "bidirectional"))
      (node (ref "IC2") (pin "8") (pinfunction "V+_8") (pintype "power_in"))
      (node (ref "R103") (pin "2") (pinfunction "2_2") (pintype "passive"))
      (node (ref "R105") (pin "1") (pinfunction "1_1") (pintype "passive"))
      (node (ref "R11") (pin "1") (pinfunction "1_1") (pintype "passive"))
      (node (ref "R111") (pin "2") (pinfunction "2_2") (pintype "passive"))
      (node (ref "R112") (pin "2") (pinfunction "2_2") (pintype "passive"))
      (node (ref "R113") (pin "1") (pinfunction "1_1") (pintype "passive"))
      (node (ref "R114") (pin "1") (pinfunction "1_1") (pintype "passive"))
      (node (ref "R115") (pin "1") (pinfunction "1_1") (pintype "passive"))
      (node (ref "R26") (pin "1") (pinfunction "1_1") (pintype "passive"))
      (node (ref "R6") (pin "1") (pinfunction "1_1") (pintype "passive"))
      (node (ref "RSENSE1") (pin "I2") (pinfunction "I2_I2") (pintype "bidirectional"))
      (node (ref "R_SENSE1") (pin "I1") (pinfunction "I1_I1") (pintype "bidirectional"))
      (node (ref "U$1") (pin "2") (pinfunction "C_2") (pintype "passive"))
      (node (ref "U$100") (pin "3") (pinfunction "NC2_3") (pintype "bidirectional"))
      (node (ref "U$2") (pin "3") (pinfunction "VCC_3") (pintype "bidirectional"))
      (node (ref "U$3") (pin "3") (pinfunction "VCC_3") (pintype "bidirectional"))
      (node (ref "U$4") (pin "3") (pinfunction "FB_3") (pintype "bidirectional"))
      (node (ref "U$4") (pin "4") (pinfunction "VOS_4") (pintype "bidirectional"))
      (node (ref "U$5") (pin "16") (pinfunction "AVCC_16") (pintype "bidirectional"))
      (node (ref "U$5") (pin "2") (pinfunction "DVCC_2") (pintype "bidirectional"))
      (node (ref "U$6") (pin "3") (pinfunction "VIN_3") (pintype "bidirectional"))
      (node (ref "VCC") (pin "1") (pinfunction "1_1") (pintype "passive"))
    )
    (net (code "77") (name "unconnected-(U$5-P1.0{slash}TACLK{slash}ADC10CLK-Pad31)") (class "Default")
      (node (ref "U$5") (pin "31") (pinfunction "P1.0/TACLK/ADC10CLK_31") (pintype "bidirectional"))
    )
    (net (code "78") (name "unconnected-(U$5-P2.0{slash}ACLK{slash}A0-Pad8)") (class "Default")
      (node (ref "U$5") (pin "8") (pinfunction "P2.0/ACLK/A0_8") (pintype "bidirectional"))
    )
    (net (code "79") (name "unconnected-(U$5-P2.3{slash}TA1{slash}A3{slash}VREF−{slash}VEREF--Pad29)") (class "Default")
      (node (ref "U$5") (pin "29") (pinfunction "P2.3/TA1/A3/VREF−/VEREF-_29") (pintype "bidirectional"))
    )
    (net (code "80") (name "unconnected-(U$5-P2.4{slash}TA2{slash}A4{slash}VREF+{slash}VEREF+-Pad30)") (class "Default")
      (node (ref "U$5") (pin "30") (pinfunction "P2.4/TA2/A4/VREF+/VEREF+_30") (pintype "bidirectional"))
    )
    (net (code "81") (name "unconnected-(U$5-P2.5{slash}ROSC-Pad3)") (class "Default")
      (node (ref "U$5") (pin "3") (pinfunction "P2.5/ROSC_3") (pintype "bidirectional"))
    )
    (net (code "82") (name "unconnected-(U$5-P3.0{slash}UCB0STE{slash}UCA0CLK{slash}A5-Pad11)") (class "Default")
      (node (ref "U$5") (pin "11") (pinfunction "P3.0/UCB0STE/UCA0CLK/A5_11") (pintype "bidirectional"))
    )
    (net (code "83") (name "unconnected-(U$5-P3.3{slash}UCB0CLK{slash}UCA0STE-Pad14)") (class "Default")
      (node (ref "U$5") (pin "14") (pinfunction "P3.3/UCB0CLK/UCA0STE_14") (pintype "bidirectional"))
    )
    (net (code "84") (name "unconnected-(U$5-P3.4{slash}UCA0TXD{slash}UCA0SIMO-Pad25)") (class "Default")
      (node (ref "U$5") (pin "25") (pinfunction "P3.4/UCA0TXD/UCA0SIMO_25") (pintype "bidirectional"))
    )
    (net (code "85") (name "unconnected-(U$5-P3.5{slash}UCA0RXD{slash}UCA0SOMI-Pad26)") (class "Default")
      (node (ref "U$5") (pin "26") (pinfunction "P3.5/UCA0RXD/UCA0SOMI_26") (pintype "bidirectional"))
    )
    (net (code "86") (name "unconnected-(U$5-P4.2{slash}TB2-Pad19)") (class "Default")
      (node (ref "U$5") (pin "19") (pinfunction "P4.2/TB2_19") (pintype "bidirectional"))
    )
    (net (code "87") (name "unconnected-(U$5-P4.7{slash}TBCLK-Pad24)") (class "Default")
      (node (ref "U$5") (pin "24") (pinfunction "P4.7/TBCLK_24") (pintype "bidirectional"))
    )
    (net (code "88") (name "unconnected-(U$6-PG-Pad6)") (class "Default")
      (node (ref "U$6") (pin "6") (pinfunction "PG_6") (pintype "bidirectional"))
    )
    (net (code "89") (name "unconnected-(U$100-IN-Pad2)") (class "Default")
      (node (ref "U$100") (pin "2") (pinfunction "IN_2") (pintype "bidirectional"))
    )
    (net (code "90") (name "unconnected-(U$100-NC1-Pad1)") (class "Default")
      (node (ref "U$100") (pin "1") (pinfunction "NC1_1") (pintype "bidirectional"))
    )
    (net (code "91") (name "unconnected-(U$100-NC3-Pad5)") (class "Default")
      (node (ref "U$100") (pin "5") (pinfunction "NC3_5") (pintype "bidirectional"))
    )
    (net (code "92") (name "unconnected-(U$100-NC4-Pad7)") (class "Default")
      (node (ref "U$100") (pin "7") (pinfunction "NC4_7") (pintype "bidirectional"))
    )
    (net (code "93") (name "unconnected-(U$100-NC5-Pad8)") (class "Default")
      (node (ref "U$100") (pin "8") (pinfunction "NC5_8") (pintype "bidirectional"))
    )
    (net (code "94") (name "unconnected-(U$101-OC-Pad5)") (class "Default")
      (node (ref "U$101") (pin "5") (pinfunction "OC_5") (pintype "bidirectional"))
    )
    (net (code "95") (name "unconnected-(U$102-OC-Pad5)") (class "Default")
      (node (ref "U$102") (pin "5") (pinfunction "OC_5") (pintype "bidirectional"))
    )
    (net (code "96") (name "unconnected-(U$103-OC-Pad5)") (class "Default")
      (node (ref "U$103") (pin "5") (pinfunction "OC_5") (pintype "bidirectional"))
    )
  )
)
